# slave.net
KiCad netlist of a schematic drawn in Altium Designer
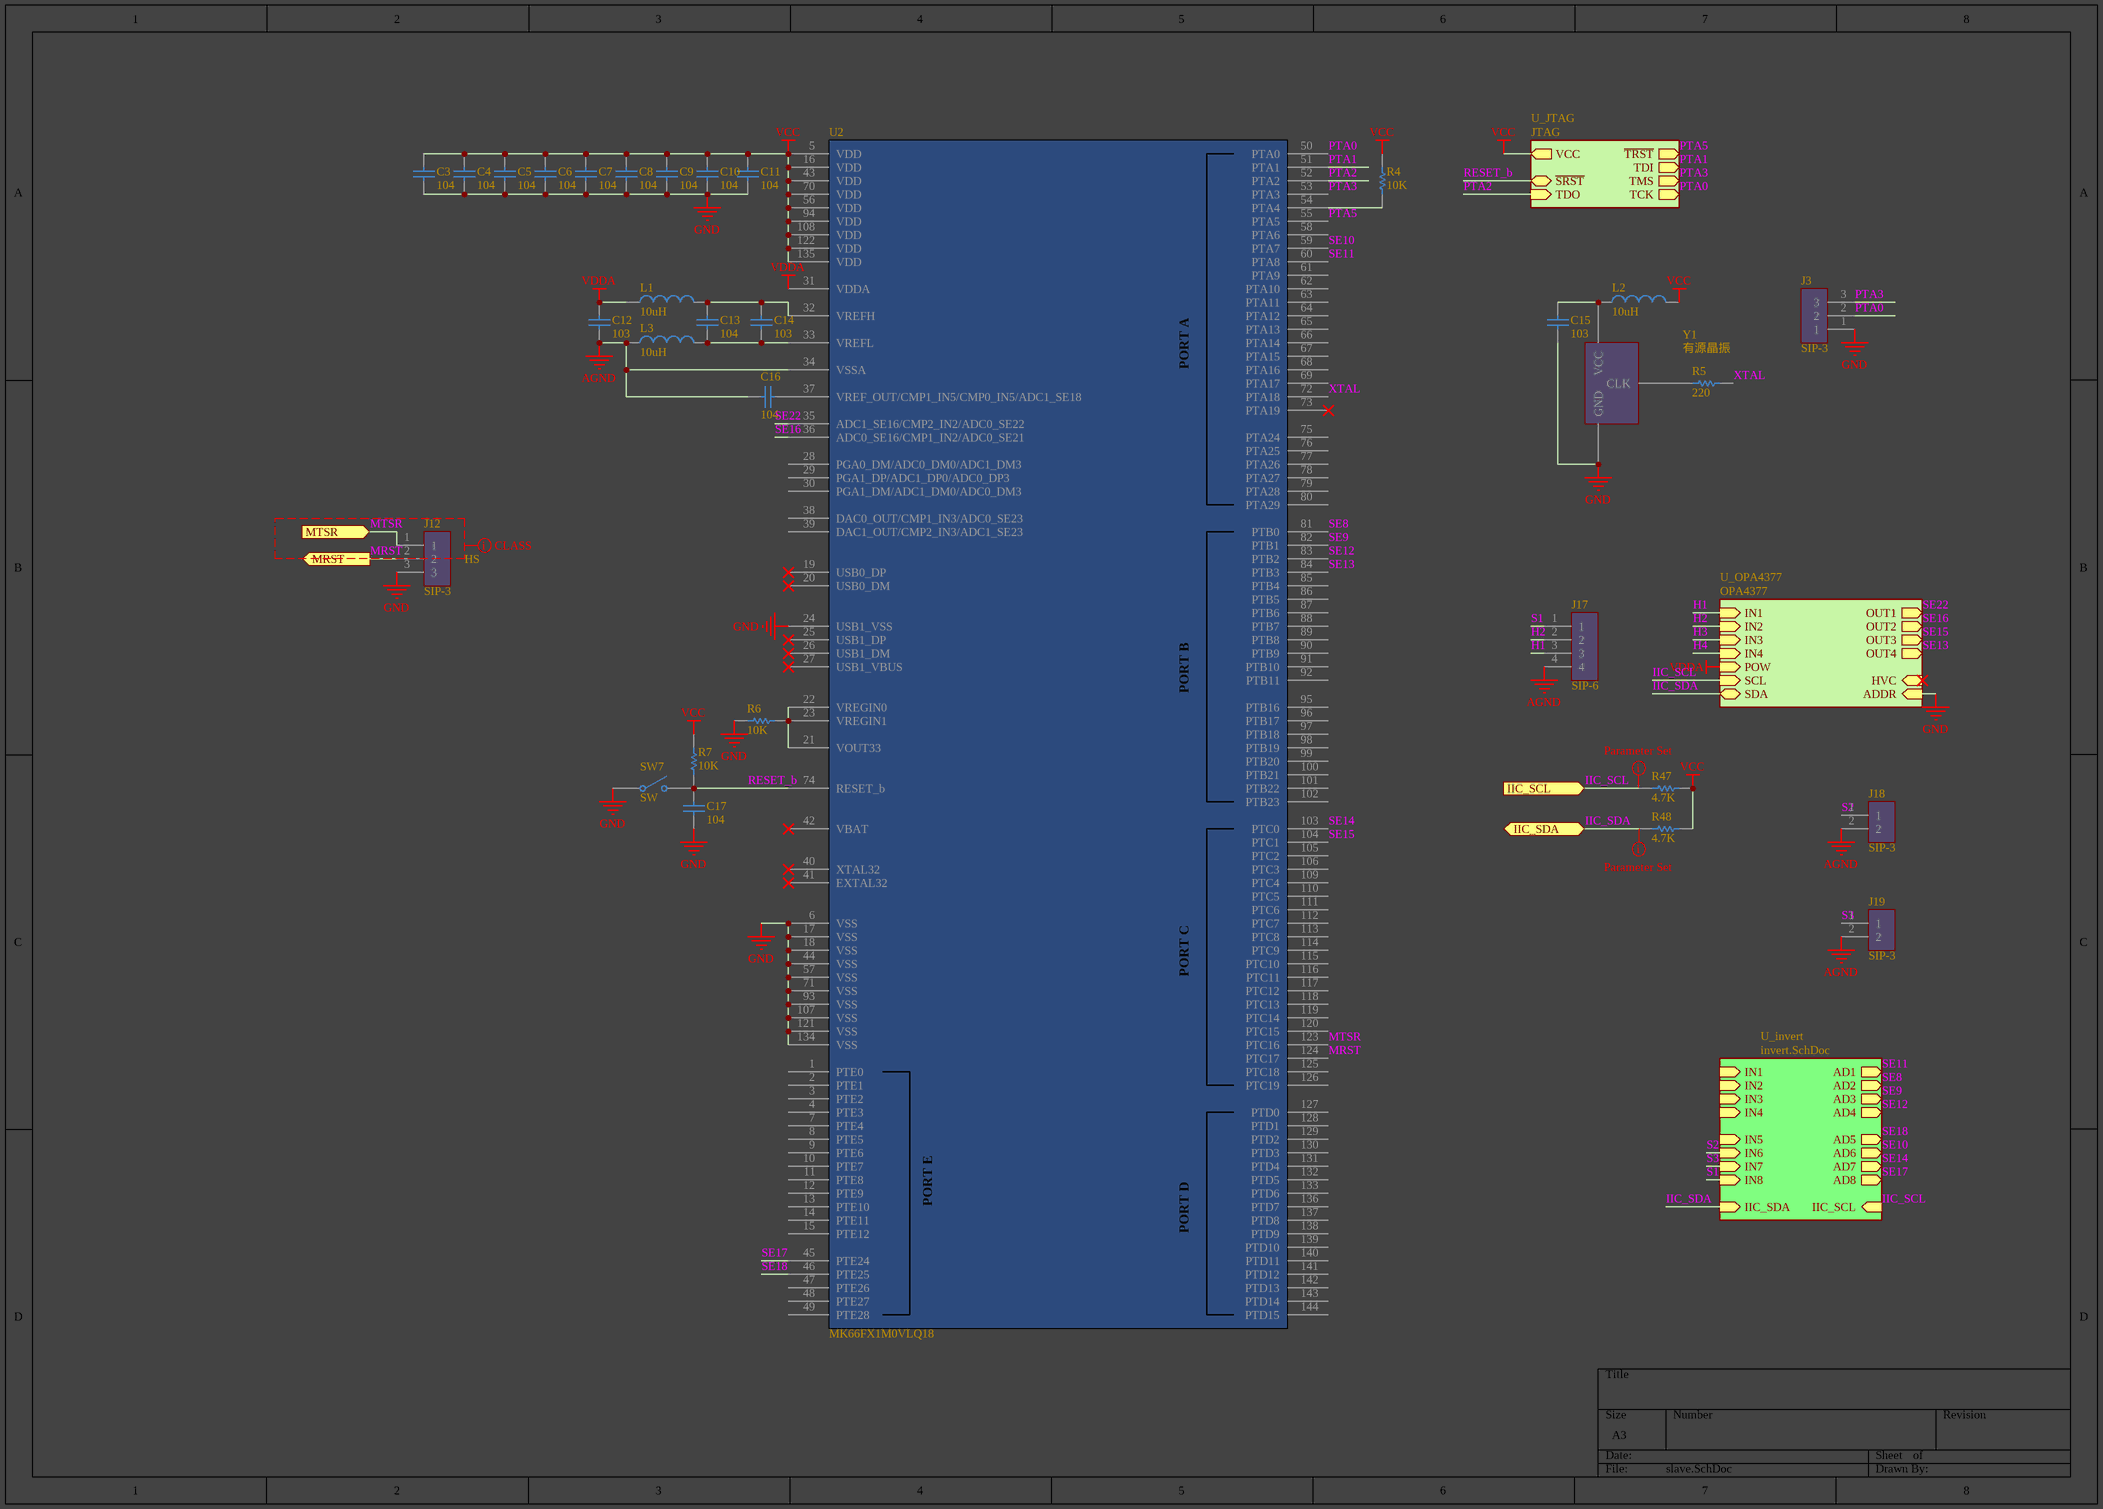
[diagram p0: slave.SchDoc]

(export (version "E")
  (design (tool "Eeschema 10.0.6"))
  (components
    (comp (ref "C3")
      (value "104")
      (footprint "C0603")
      (description "Capacitor")
      (fields (field (name "PUBLISHER") "Altium Limited"))
      (libsource (lib "iMag") (part "电容"))
    )
    (comp (ref "C4")
      (value "104")
      (footprint "C0603")
      (description "Capacitor")
      (fields (field (name "PUBLISHER") "Altium Limited"))
      (libsource (lib "iMag") (part "电容"))
    )
    (comp (ref "C5")
      (value "104")
      (footprint "C0603")
      (description "Capacitor")
      (fields (field (name "PUBLISHER") "Altium Limited"))
      (libsource (lib "iMag") (part "电容"))
    )
    (comp (ref "C6")
      (value "104")
      (footprint "C0603")
      (description "Capacitor")
      (fields (field (name "PUBLISHER") "Altium Limited"))
      (libsource (lib "iMag") (part "电容"))
    )
    (comp (ref "C7")
      (value "104")
      (footprint "C0603")
      (description "Capacitor")
      (fields (field (name "PUBLISHER") "Altium Limited"))
      (libsource (lib "iMag") (part "电容"))
    )
    (comp (ref "C8")
      (value "104")
      (footprint "C0603")
      (description "Capacitor")
      (fields (field (name "PUBLISHER") "Altium Limited"))
      (libsource (lib "iMag") (part "电容"))
    )
    (comp (ref "C9")
      (value "104")
      (footprint "C0603")
      (description "Capacitor")
      (fields (field (name "PUBLISHER") "Altium Limited"))
      (libsource (lib "iMag") (part "电容"))
    )
    (comp (ref "C10")
      (value "104")
      (footprint "C0603")
      (description "Capacitor")
      (fields (field (name "PUBLISHER") "Altium Limited"))
      (libsource (lib "iMag") (part "电容"))
    )
    (comp (ref "C11")
      (value "104")
      (footprint "C0603")
      (description "Capacitor")
      (fields (field (name "PUBLISHER") "Altium Limited"))
      (libsource (lib "iMag") (part "电容"))
    )
    (comp (ref "C12")
      (value "103")
      (footprint "C0603")
      (description "Capacitor")
      (fields (field (name "PUBLISHER") "Altium Limited"))
      (libsource (lib "iMag") (part "电容"))
    )
    (comp (ref "C13")
      (value "104")
      (footprint "C0603")
      (description "Capacitor")
      (fields (field (name "PUBLISHER") "Altium Limited"))
      (libsource (lib "iMag") (part "电容"))
    )
    (comp (ref "C14")
      (value "103")
      (footprint "C0603")
      (description "Capacitor")
      (fields (field (name "PUBLISHER") "Altium Limited"))
      (libsource (lib "iMag") (part "电容"))
    )
    (comp (ref "C15")
      (value "103")
      (footprint "C0603")
      (description "Capacitor")
      (fields (field (name "PUBLISHER") "Altium Limited"))
      (libsource (lib "iMag") (part "电容"))
    )
    (comp (ref "C16")
      (value "104")
      (footprint "C0402")
      (description "Capacitor")
      (fields (field (name "PUBLISHER") "Altium Limited"))
      (libsource (lib "iMag") (part "电容"))
    )
    (comp (ref "C17")
      (value "104")
      (footprint "C0603")
      (description "Capacitor")
      (fields (field (name "PUBLISHER") "Altium Limited"))
      (libsource (lib "iMag") (part "电容"))
    )
    (comp (ref "J3") (value "SIP-3") (footprint "2.0排针3P") (libsource (lib "iMag") (part "SIP-3")))
    (comp (ref "J12") (value "SIP-3") (footprint "2.0排针3P") (libsource (lib "") (part "SIP-3_1")))
    (comp (ref "J17") (value "SIP-6") (footprint "2.0排针4P") (libsource (lib "iMag") (part "SIP-4")))
    (comp (ref "J18") (value "SIP-3") (footprint "GH1.25-2P") (libsource (lib "iMag") (part "SIP-2")))
    (comp (ref "J19") (value "SIP-3") (footprint "GH1.25-2P") (libsource (lib "iMag") (part "SIP-2")))
    (comp (ref "L1") (value "10uH") (footprint "L0603") (libsource (lib "iMag") (part "电感")))
    (comp (ref "L2") (value "10uH") (footprint "L0603") (libsource (lib "iMag") (part "电感")))
    (comp (ref "L3") (value "10uH") (footprint "L0603") (libsource (lib "iMag") (part "电感")))
    (comp (ref "R4")
      (value "10K")
      (footprint "R0603")
      (description "Resistor")
      (fields (field (name "PUBLISHER") "Altium Limited"))
      (libsource (lib "iMag") (part "电阻"))
    )
    (comp (ref "R5")
      (value "220")
      (footprint "R0402")
      (description "Resistor")
      (fields (field (name "PUBLISHER") "Altium Limited"))
      (libsource (lib "iMag") (part "电阻"))
    )
    (comp (ref "R6")
      (value "10K")
      (footprint "R0603")
      (description "Resistor")
      (fields (field (name "PUBLISHER") "Altium Limited"))
      (libsource (lib "iMag") (part "电阻"))
    )
    (comp (ref "R7")
      (value "10K")
      (footprint "R0603")
      (description "Resistor")
      (fields (field (name "PUBLISHER") "Altium Limited"))
      (libsource (lib "iMag") (part "电阻"))
    )
    (comp (ref "R47")
      (value "4.7K")
      (footprint "R0603")
      (description "Resistor")
      (fields (field (name "PUBLISHER") "Altium Limited"))
      (libsource (lib "iMag") (part "电阻"))
    )
    (comp (ref "R48")
      (value "4.7K")
      (footprint "R0603")
      (description "Resistor")
      (fields (field (name "PUBLISHER") "Altium Limited"))
      (libsource (lib "iMag") (part "电阻"))
    )
    (comp (ref "SW7")
      (value "SW")
      (footprint "按键微动开关2")
      (description "Single-Pole, Single-Throw Switch")
      (libsource (lib "iMag") (part "Switch"))
    )
    (comp (ref "U2")
      (value "MK66FX1M0VLQ18")
      (footprint "LQFP144 20X20")
      (libsource (lib "iMag") (part "MK66"))
    )
    (comp (ref "Y1") (value "有源晶振") (footprint "OSC 5032-4P") (libsource (lib "iMag") (part "有源晶振")))
  )
  (nets
    (net (code "1") (name "/H1") (class "Default")
      (node (ref "J17") (pin "3") (pinfunction "3_3") (pintype "passive"))
    )
    (net (code "2") (name "/H2") (class "Default")
      (node (ref "J17") (pin "2") (pinfunction "2_2") (pintype "passive"))
    )
    (net (code "6") (name "/IIC_SCL") (class "Default")
      (node (ref "R47") (pin "2") (pinfunction "2_2") (pintype "passive"))
    )
    (net (code "7") (name "/IIC_SDA") (class "Default")
      (node (ref "R48") (pin "2") (pinfunction "2_2") (pintype "passive"))
    )
    (net (code "13") (name "/MRST") (class "Default")
      (node (ref "J12") (pin "2") (pinfunction "2_2") (pintype "passive"))
      (node (ref "U2") (pin "124") (pinfunction "PTC17_124") (pintype "passive"))
    )
    (net (code "14") (name "/MTSR") (class "Default")
      (node (ref "J12") (pin "1") (pinfunction "1_1") (pintype "passive"))
      (node (ref "U2") (pin "123") (pinfunction "PTC16_123") (pintype "passive"))
    )
    (net (code "15") (name "/PTA0") (class "Default")
      (node (ref "J3") (pin "2") (pinfunction "2_2") (pintype "passive"))
      (node (ref "U2") (pin "50") (pinfunction "PTA0_50") (pintype "passive"))
    )
    (net (code "16") (name "/PTA1") (class "Default")
      (node (ref "U2") (pin "51") (pinfunction "PTA1_51") (pintype "passive"))
    )
    (net (code "17") (name "/PTA2") (class "Default")
      (node (ref "U2") (pin "52") (pinfunction "PTA2_52") (pintype "passive"))
    )
    (net (code "18") (name "/PTA3") (class "Default")
      (node (ref "J3") (pin "3") (pinfunction "3_3") (pintype "passive"))
      (node (ref "U2") (pin "53") (pinfunction "PTA3_53") (pintype "passive"))
    )
    (net (code "19") (name "/PTA5") (class "Default")
      (node (ref "U2") (pin "55") (pinfunction "PTA5_55") (pintype "passive"))
    )
    (net (code "20") (name "/RESET_b") (class "Default")
      (node (ref "C17") (pin "2") (pinfunction "2_2") (pintype "passive"))
      (node (ref "R7") (pin "1") (pinfunction "1_1") (pintype "passive"))
      (node (ref "SW7") (pin "2") (pinfunction "NO_2") (pintype "passive"))
      (node (ref "U2") (pin "74") (pinfunction "RESET_b_74") (pintype "passive"))
    )
    (net (code "21") (name "/S1") (class "Default")
      (node (ref "J17") (pin "1") (pinfunction "1_1") (pintype "passive"))
    )
    (net (code "22") (name "/S2") (class "Default")
      (node (ref "J18") (pin "1") (pinfunction "1_1") (pintype "passive"))
    )
    (net (code "23") (name "/S3") (class "Default")
      (node (ref "J19") (pin "1") (pinfunction "1_1") (pintype "passive"))
    )
    (net (code "24") (name "/SE8") (class "Default")
      (node (ref "U2") (pin "81") (pinfunction "PTB0_81") (pintype "passive"))
    )
    (net (code "25") (name "/SE9") (class "Default")
      (node (ref "U2") (pin "82") (pinfunction "PTB1_82") (pintype "passive"))
    )
    (net (code "26") (name "/SE10") (class "Default")
      (node (ref "U2") (pin "59") (pinfunction "PTA7_59") (pintype "passive"))
    )
    (net (code "27") (name "/SE11") (class "Default")
      (node (ref "U2") (pin "60") (pinfunction "PTA8_60") (pintype "passive"))
    )
    (net (code "28") (name "/SE12") (class "Default")
      (node (ref "U2") (pin "83") (pinfunction "PTB2_83") (pintype "passive"))
    )
    (net (code "29") (name "/SE13") (class "Default")
      (node (ref "U2") (pin "84") (pinfunction "PTB3_84") (pintype "passive"))
    )
    (net (code "30") (name "/SE14") (class "Default")
      (node (ref "U2") (pin "103") (pinfunction "PTC0_103") (pintype "passive"))
    )
    (net (code "31") (name "/SE15") (class "Default")
      (node (ref "U2") (pin "104") (pinfunction "PTC1_104") (pintype "passive"))
    )
    (net (code "32") (name "/SE16") (class "Default")
      (node (ref "U2") (pin "36") (pinfunction "ADC0_SE16/CMP1_IN2/ADC0_SE21_36") (pintype "passive"))
    )
    (net (code "33") (name "/SE17") (class "Default")
      (node (ref "U2") (pin "45") (pinfunction "PTE24_45") (pintype "passive"))
    )
    (net (code "34") (name "/SE18") (class "Default")
      (node (ref "U2") (pin "46") (pinfunction "PTE25_46") (pintype "passive"))
    )
    (net (code "35") (name "/SE22") (class "Default")
      (node (ref "U2") (pin "35") (pinfunction "ADC1_SE16/CMP2_IN2/ADC0_SE22_35") (pintype "passive"))
    )
    (net (code "36") (name "/XTAL") (class "Default")
      (node (ref "R5") (pin "1") (pinfunction "1_1") (pintype "passive"))
      (node (ref "U2") (pin "72") (pinfunction "PTA18_72") (pintype "passive"))
    )
    (net (code "37") (name "AGND") (class "Default")
      (node (ref "C12") (pin "1") (pinfunction "1_1") (pintype "passive"))
      (node (ref "C16") (pin "1") (pinfunction "1_1") (pintype "passive"))
      (node (ref "J17") (pin "4") (pinfunction "4_4") (pintype "passive"))
      (node (ref "J18") (pin "2") (pinfunction "2_2") (pintype "passive"))
      (node (ref "J19") (pin "2") (pinfunction "2_2") (pintype "passive"))
      (node (ref "L3") (pin "1") (pinfunction "1_1") (pintype "passive"))
      (node (ref "U2") (pin "34") (pinfunction "VSSA_34") (pintype "passive"))
    )
    (net (code "38") (name "GND") (class "Default")
      (node (ref "C10") (pin "1") (pinfunction "1_1") (pintype "passive"))
      (node (ref "C11") (pin "1") (pinfunction "1_1") (pintype "passive"))
      (node (ref "C15") (pin "1") (pinfunction "1_1") (pintype "passive"))
      (node (ref "C17") (pin "1") (pinfunction "1_1") (pintype "passive"))
      (node (ref "C3") (pin "1") (pinfunction "1_1") (pintype "passive"))
      (node (ref "C4") (pin "1") (pinfunction "1_1") (pintype "passive"))
      (node (ref "C5") (pin "1") (pinfunction "1_1") (pintype "passive"))
      (node (ref "C6") (pin "1") (pinfunction "1_1") (pintype "passive"))
      (node (ref "C7") (pin "1") (pinfunction "1_1") (pintype "passive"))
      (node (ref "C8") (pin "1") (pinfunction "1_1") (pintype "passive"))
      (node (ref "C9") (pin "1") (pinfunction "1_1") (pintype "passive"))
      (node (ref "J12") (pin "3") (pinfunction "3_3") (pintype "passive"))
      (node (ref "J3") (pin "1") (pinfunction "1_1") (pintype "passive"))
      (node (ref "R6") (pin "2") (pinfunction "2_2") (pintype "passive"))
      (node (ref "SW7") (pin "1") (pinfunction "COMMON_1") (pintype "passive"))
      (node (ref "U2") (pin "107") (pinfunction "VSS_107") (pintype "passive"))
      (node (ref "U2") (pin "121") (pinfunction "VSS_121") (pintype "passive"))
      (node (ref "U2") (pin "134") (pinfunction "VSS_134") (pintype "passive"))
      (node (ref "U2") (pin "17") (pinfunction "VSS_17") (pintype "passive"))
      (node (ref "U2") (pin "18") (pinfunction "VSS_18") (pintype "passive"))
      (node (ref "U2") (pin "24") (pinfunction "USB1_VSS_24") (pintype "passive"))
      (node (ref "U2") (pin "44") (pinfunction "VSS_44") (pintype "passive"))
      (node (ref "U2") (pin "57") (pinfunction "VSS_57") (pintype "passive"))
      (node (ref "U2") (pin "6") (pinfunction "VSS_6") (pintype "passive"))
      (node (ref "U2") (pin "71") (pinfunction "VSS_71") (pintype "passive"))
      (node (ref "U2") (pin "93") (pinfunction "VSS_93") (pintype "passive"))
      (node (ref "Y1") (pin "2") (pinfunction "GND_2") (pintype "passive"))
    )
    (net (code "39") (name "Net-(U2-PTA4)") (class "Default")
      (node (ref "R4") (pin "2") (pinfunction "2_2") (pintype "passive"))
      (node (ref "U2") (pin "54") (pinfunction "PTA4_54") (pintype "passive"))
    )
    (net (code "40") (name "Net-(U2-VOUT33)") (class "Default")
      (node (ref "R6") (pin "1") (pinfunction "1_1") (pintype "passive"))
      (node (ref "U2") (pin "21") (pinfunction "VOUT33_21") (pintype "passive"))
      (node (ref "U2") (pin "22") (pinfunction "VREGIN0_22") (pintype "passive"))
      (node (ref "U2") (pin "23") (pinfunction "VREGIN1_23") (pintype "passive"))
    )
    (net (code "41") (name "Net-(U2-VREFH)") (class "Default")
      (node (ref "C13") (pin "2") (pinfunction "2_2") (pintype "passive"))
      (node (ref "C14") (pin "2") (pinfunction "2_2") (pintype "passive"))
      (node (ref "L1") (pin "2") (pinfunction "2_2") (pintype "passive"))
      (node (ref "U2") (pin "32") (pinfunction "VREFH_32") (pintype "passive"))
    )
    (net (code "42") (name "Net-(U2-VREFL)") (class "Default")
      (node (ref "C13") (pin "1") (pinfunction "1_1") (pintype "passive"))
      (node (ref "C14") (pin "1") (pinfunction "1_1") (pintype "passive"))
      (node (ref "L3") (pin "2") (pinfunction "2_2") (pintype "passive"))
      (node (ref "U2") (pin "33") (pinfunction "VREFL_33") (pintype "passive"))
    )
    (net (code "43") (name "Net-(U2-VREF_OUT{slash}CMP1_IN5{slash}CMP0_IN5{slash}ADC1_SE18)") (class "Default")
      (node (ref "C16") (pin "2") (pinfunction "2_2") (pintype "passive"))
      (node (ref "U2") (pin "37") (pinfunction "VREF_OUT/CMP1_IN5/CMP0_IN5/ADC1_SE18_37") (pintype "passive"))
    )
    (net (code "44") (name "Net-(Y1-CLK)") (class "Default")
      (node (ref "R5") (pin "2") (pinfunction "2_2") (pintype "passive"))
      (node (ref "Y1") (pin "3") (pinfunction "CLK_3") (pintype "passive"))
    )
    (net (code "45") (name "Net-(Y1-VCC)") (class "Default")
      (node (ref "C15") (pin "2") (pinfunction "2_2") (pintype "passive"))
      (node (ref "L2") (pin "1") (pinfunction "1_1") (pintype "passive"))
      (node (ref "Y1") (pin "4") (pinfunction "VCC_4") (pintype "passive"))
    )
    (net (code "46") (name "VCC") (class "Default")
      (node (ref "C10") (pin "2") (pinfunction "2_2") (pintype "passive"))
      (node (ref "C11") (pin "2") (pinfunction "2_2") (pintype "passive"))
      (node (ref "C3") (pin "2") (pinfunction "2_2") (pintype "passive"))
      (node (ref "C4") (pin "2") (pinfunction "2_2") (pintype "passive"))
      (node (ref "C5") (pin "2") (pinfunction "2_2") (pintype "passive"))
      (node (ref "C6") (pin "2") (pinfunction "2_2") (pintype "passive"))
      (node (ref "C7") (pin "2") (pinfunction "2_2") (pintype "passive"))
      (node (ref "C8") (pin "2") (pinfunction "2_2") (pintype "passive"))
      (node (ref "C9") (pin "2") (pinfunction "2_2") (pintype "passive"))
      (node (ref "L2") (pin "2") (pinfunction "2_2") (pintype "passive"))
      (node (ref "R4") (pin "1") (pinfunction "1_1") (pintype "passive"))
      (node (ref "R47") (pin "1") (pinfunction "1_1") (pintype "passive"))
      (node (ref "R48") (pin "1") (pinfunction "1_1") (pintype "passive"))
      (node (ref "R7") (pin "2") (pinfunction "2_2") (pintype "passive"))
      (node (ref "U2") (pin "108") (pinfunction "VDD_108") (pintype "passive"))
      (node (ref "U2") (pin "122") (pinfunction "VDD_122") (pintype "passive"))
      (node (ref "U2") (pin "135") (pinfunction "VDD_135") (pintype "passive"))
      (node (ref "U2") (pin "16") (pinfunction "VDD_16") (pintype "passive"))
      (node (ref "U2") (pin "43") (pinfunction "VDD_43") (pintype "passive"))
      (node (ref "U2") (pin "5") (pinfunction "VDD_5") (pintype "passive"))
      (node (ref "U2") (pin "56") (pinfunction "VDD_56") (pintype "passive"))
      (node (ref "U2") (pin "70") (pinfunction "VDD_70") (pintype "passive"))
      (node (ref "U2") (pin "94") (pinfunction "VDD_94") (pintype "passive"))
    )
    (net (code "47") (name "VDDA") (class "Default")
      (node (ref "C12") (pin "2") (pinfunction "2_2") (pintype "passive"))
      (node (ref "L1") (pin "1") (pinfunction "1_1") (pintype "passive"))
      (node (ref "U2") (pin "31") (pinfunction "VDDA_31") (pintype "passive"))
    )
    (net (code "48") (name "unconnected-(U2-DAC0_OUT{slash}CMP1_IN3{slash}ADC0_SE23-Pad38)") (class "Default")
      (node (ref "U2") (pin "38") (pinfunction "DAC0_OUT/CMP1_IN3/ADC0_SE23_38") (pintype "passive"))
    )
    (net (code "49") (name "unconnected-(U2-DAC1_OUT{slash}CMP2_IN3{slash}ADC1_SE23-Pad39)") (class "Default")
      (node (ref "U2") (pin "39") (pinfunction "DAC1_OUT/CMP2_IN3/ADC1_SE23_39") (pintype "passive"))
    )
    (net (code "50") (name "unconnected-(U2-EXTAL32-Pad41)") (class "Default")
      (node (ref "U2") (pin "41") (pinfunction "EXTAL32_41") (pintype "passive+no_connect"))
    )
    (net (code "51") (name "unconnected-(U2-PGA0_DM{slash}ADC0_DM0{slash}ADC1_DM3-Pad28)") (class "Default")
      (node (ref "U2") (pin "28") (pinfunction "PGA0_DM/ADC0_DM0/ADC1_DM3_28") (pintype "passive"))
    )
    (net (code "52") (name "unconnected-(U2-PGA1_DM{slash}ADC1_DM0{slash}ADC0_DM3-Pad30)") (class "Default")
      (node (ref "U2") (pin "30") (pinfunction "PGA1_DM/ADC1_DM0/ADC0_DM3_30") (pintype "passive"))
    )
    (net (code "53") (name "unconnected-(U2-PGA1_DP{slash}ADC1_DP0{slash}ADC0_DP3-Pad29)") (class "Default")
      (node (ref "U2") (pin "29") (pinfunction "PGA1_DP/ADC1_DP0/ADC0_DP3_29") (pintype "passive"))
    )
    (net (code "54") (name "unconnected-(U2-PTA6-Pad58)") (class "Default")
      (node (ref "U2") (pin "58") (pinfunction "PTA6_58") (pintype "passive"))
    )
    (net (code "55") (name "unconnected-(U2-PTA9-Pad61)") (class "Default")
      (node (ref "U2") (pin "61") (pinfunction "PTA9_61") (pintype "passive"))
    )
    (net (code "56") (name "unconnected-(U2-PTA10-Pad62)") (class "Default")
      (node (ref "U2") (pin "62") (pinfunction "PTA10_62") (pintype "passive"))
    )
    (net (code "57") (name "unconnected-(U2-PTA11-Pad63)") (class "Default")
      (node (ref "U2") (pin "63") (pinfunction "PTA11_63") (pintype "passive"))
    )
    (net (code "58") (name "unconnected-(U2-PTA12-Pad64)") (class "Default")
      (node (ref "U2") (pin "64") (pinfunction "PTA12_64") (pintype "passive"))
    )
    (net (code "59") (name "unconnected-(U2-PTA13-Pad65)") (class "Default")
      (node (ref "U2") (pin "65") (pinfunction "PTA13_65") (pintype "passive"))
    )
    (net (code "60") (name "unconnected-(U2-PTA14-Pad66)") (class "Default")
      (node (ref "U2") (pin "66") (pinfunction "PTA14_66") (pintype "passive"))
    )
    (net (code "61") (name "unconnected-(U2-PTA15-Pad67)") (class "Default")
      (node (ref "U2") (pin "67") (pinfunction "PTA15_67") (pintype "passive"))
    )
    (net (code "62") (name "unconnected-(U2-PTA16-Pad68)") (class "Default")
      (node (ref "U2") (pin "68") (pinfunction "PTA16_68") (pintype "passive"))
    )
    (net (code "63") (name "unconnected-(U2-PTA17-Pad69)") (class "Default")
      (node (ref "U2") (pin "69") (pinfunction "PTA17_69") (pintype "passive"))
    )
    (net (code "64") (name "unconnected-(U2-PTA19-Pad73)") (class "Default")
      (node (ref "U2") (pin "73") (pinfunction "PTA19_73") (pintype "passive+no_connect"))
    )
    (net (code "65") (name "unconnected-(U2-PTA24-Pad75)") (class "Default")
      (node (ref "U2") (pin "75") (pinfunction "PTA24_75") (pintype "passive"))
    )
    (net (code "66") (name "unconnected-(U2-PTA25-Pad76)") (class "Default")
      (node (ref "U2") (pin "76") (pinfunction "PTA25_76") (pintype "passive"))
    )
    (net (code "67") (name "unconnected-(U2-PTA26-Pad77)") (class "Default")
      (node (ref "U2") (pin "77") (pinfunction "PTA26_77") (pintype "passive"))
    )
    (net (code "68") (name "unconnected-(U2-PTA27-Pad78)") (class "Default")
      (node (ref "U2") (pin "78") (pinfunction "PTA27_78") (pintype "passive"))
    )
    (net (code "69") (name "unconnected-(U2-PTA28-Pad79)") (class "Default")
      (node (ref "U2") (pin "79") (pinfunction "PTA28_79") (pintype "passive"))
    )
    (net (code "70") (name "unconnected-(U2-PTA29-Pad80)") (class "Default")
      (node (ref "U2") (pin "80") (pinfunction "PTA29_80") (pintype "passive"))
    )
    (net (code "71") (name "unconnected-(U2-PTB4-Pad85)") (class "Default")
      (node (ref "U2") (pin "85") (pinfunction "PTB4_85") (pintype "passive"))
    )
    (net (code "72") (name "unconnected-(U2-PTB5-Pad86)") (class "Default")
      (node (ref "U2") (pin "86") (pinfunction "PTB5_86") (pintype "passive"))
    )
    (net (code "73") (name "unconnected-(U2-PTB6-Pad87)") (class "Default")
      (node (ref "U2") (pin "87") (pinfunction "PTB6_87") (pintype "passive"))
    )
    (net (code "74") (name "unconnected-(U2-PTB7-Pad88)") (class "Default")
      (node (ref "U2") (pin "88") (pinfunction "PTB7_88") (pintype "passive"))
    )
    (net (code "75") (name "unconnected-(U2-PTB8-Pad89)") (class "Default")
      (node (ref "U2") (pin "89") (pinfunction "PTB8_89") (pintype "passive"))
    )
    (net (code "76") (name "unconnected-(U2-PTB9-Pad90)") (class "Default")
      (node (ref "U2") (pin "90") (pinfunction "PTB9_90") (pintype "passive"))
    )
    (net (code "77") (name "unconnected-(U2-PTB10-Pad91)") (class "Default")
      (node (ref "U2") (pin "91") (pinfunction "PTB10_91") (pintype "passive"))
    )
    (net (code "78") (name "unconnected-(U2-PTB11-Pad92)") (class "Default")
      (node (ref "U2") (pin "92") (pinfunction "PTB11_92") (pintype "passive"))
    )
    (net (code "79") (name "unconnected-(U2-PTB16-Pad95)") (class "Default")
      (node (ref "U2") (pin "95") (pinfunction "PTB16_95") (pintype "passive"))
    )
    (net (code "80") (name "unconnected-(U2-PTB17-Pad96)") (class "Default")
      (node (ref "U2") (pin "96") (pinfunction "PTB17_96") (pintype "passive"))
    )
    (net (code "81") (name "unconnected-(U2-PTB18-Pad97)") (class "Default")
      (node (ref "U2") (pin "97") (pinfunction "PTB18_97") (pintype "passive"))
    )
    (net (code "82") (name "unconnected-(U2-PTB19-Pad98)") (class "Default")
      (node (ref "U2") (pin "98") (pinfunction "PTB19_98") (pintype "passive"))
    )
    (net (code "83") (name "unconnected-(U2-PTB20-Pad99)") (class "Default")
      (node (ref "U2") (pin "99") (pinfunction "PTB20_99") (pintype "passive"))
    )
    (net (code "84") (name "unconnected-(U2-PTB21-Pad100)") (class "Default")
      (node (ref "U2") (pin "100") (pinfunction "PTB21_100") (pintype "passive"))
    )
    (net (code "85") (name "unconnected-(U2-PTB22-Pad101)") (class "Default")
      (node (ref "U2") (pin "101") (pinfunction "PTB22_101") (pintype "passive"))
    )
    (net (code "86") (name "unconnected-(U2-PTB23-Pad102)") (class "Default")
      (node (ref "U2") (pin "102") (pinfunction "PTB23_102") (pintype "passive"))
    )
    (net (code "87") (name "unconnected-(U2-PTC2-Pad105)") (class "Default")
      (node (ref "U2") (pin "105") (pinfunction "PTC2_105") (pintype "passive"))
    )
    (net (code "88") (name "unconnected-(U2-PTC3-Pad106)") (class "Default")
      (node (ref "U2") (pin "106") (pinfunction "PTC3_106") (pintype "passive"))
    )
    (net (code "89") (name "unconnected-(U2-PTC4-Pad109)") (class "Default")
      (node (ref "U2") (pin "109") (pinfunction "PTC4_109") (pintype "passive"))
    )
    (net (code "90") (name "unconnected-(U2-PTC5-Pad110)") (class "Default")
      (node (ref "U2") (pin "110") (pinfunction "PTC5_110") (pintype "passive"))
    )
    (net (code "91") (name "unconnected-(U2-PTC6-Pad111)") (class "Default")
      (node (ref "U2") (pin "111") (pinfunction "PTC6_111") (pintype "passive"))
    )
    (net (code "92") (name "unconnected-(U2-PTC7-Pad112)") (class "Default")
      (node (ref "U2") (pin "112") (pinfunction "PTC7_112") (pintype "passive"))
    )
    (net (code "93") (name "unconnected-(U2-PTC8-Pad113)") (class "Default")
      (node (ref "U2") (pin "113") (pinfunction "PTC8_113") (pintype "passive"))
    )
    (net (code "94") (name "unconnected-(U2-PTC9-Pad114)") (class "Default")
      (node (ref "U2") (pin "114") (pinfunction "PTC9_114") (pintype "passive"))
    )
    (net (code "95") (name "unconnected-(U2-PTC10-Pad115)") (class "Default")
      (node (ref "U2") (pin "115") (pinfunction "PTC10_115") (pintype "passive"))
    )
    (net (code "96") (name "unconnected-(U2-PTC11-Pad116)") (class "Default")
      (node (ref "U2") (pin "116") (pinfunction "PTC11_116") (pintype "passive"))
    )
    (net (code "97") (name "unconnected-(U2-PTC12-Pad117)") (class "Default")
      (node (ref "U2") (pin "117") (pinfunction "PTC12_117") (pintype "passive"))
    )
    (net (code "98") (name "unconnected-(U2-PTC13-Pad118)") (class "Default")
      (node (ref "U2") (pin "118") (pinfunction "PTC13_118") (pintype "passive"))
    )
    (net (code "99") (name "unconnected-(U2-PTC14-Pad119)") (class "Default")
      (node (ref "U2") (pin "119") (pinfunction "PTC14_119") (pintype "passive"))
    )
    (net (code "100") (name "unconnected-(U2-PTC15-Pad120)") (class "Default")
      (node (ref "U2") (pin "120") (pinfunction "PTC15_120") (pintype "passive"))
    )
    (net (code "101") (name "unconnected-(U2-PTC18-Pad125)") (class "Default")
      (node (ref "U2") (pin "125") (pinfunction "PTC18_125") (pintype "passive"))
    )
    (net (code "102") (name "unconnected-(U2-PTC19-Pad126)") (class "Default")
      (node (ref "U2") (pin "126") (pinfunction "PTC19_126") (pintype "passive"))
    )
    (net (code "103") (name "unconnected-(U2-PTD0-Pad127)") (class "Default")
      (node (ref "U2") (pin "127") (pinfunction "PTD0_127") (pintype "passive"))
    )
    (net (code "104") (name "unconnected-(U2-PTD1-Pad128)") (class "Default")
      (node (ref "U2") (pin "128") (pinfunction "PTD1_128") (pintype "passive"))
    )
    (net (code "105") (name "unconnected-(U2-PTD2-Pad129)") (class "Default")
      (node (ref "U2") (pin "129") (pinfunction "PTD2_129") (pintype "passive"))
    )
    (net (code "106") (name "unconnected-(U2-PTD3-Pad130)") (class "Default")
      (node (ref "U2") (pin "130") (pinfunction "PTD3_130") (pintype "passive"))
    )
    (net (code "107") (name "unconnected-(U2-PTD4-Pad131)") (class "Default")
      (node (ref "U2") (pin "131") (pinfunction "PTD4_131") (pintype "passive"))
    )
    (net (code "108") (name "unconnected-(U2-PTD5-Pad132)") (class "Default")
      (node (ref "U2") (pin "132") (pinfunction "PTD5_132") (pintype "passive"))
    )
    (net (code "109") (name "unconnected-(U2-PTD6-Pad133)") (class "Default")
      (node (ref "U2") (pin "133") (pinfunction "PTD6_133") (pintype "passive"))
    )
    (net (code "110") (name "unconnected-(U2-PTD7-Pad136)") (class "Default")
      (node (ref "U2") (pin "136") (pinfunction "PTD7_136") (pintype "passive"))
    )
    (net (code "111") (name "unconnected-(U2-PTD8-Pad137)") (class "Default")
      (node (ref "U2") (pin "137") (pinfunction "PTD8_137") (pintype "passive"))
    )
    (net (code "112") (name "unconnected-(U2-PTD9-Pad138)") (class "Default")
      (node (ref "U2") (pin "138") (pinfunction "PTD9_138") (pintype "passive"))
    )
    (net (code "113") (name "unconnected-(U2-PTD10-Pad139)") (class "Default")
      (node (ref "U2") (pin "139") (pinfunction "PTD10_139") (pintype "passive"))
    )
    (net (code "114") (name "unconnected-(U2-PTD11-Pad140)") (class "Default")
      (node (ref "U2") (pin "140") (pinfunction "PTD11_140") (pintype "passive"))
    )
    (net (code "115") (name "unconnected-(U2-PTD12-Pad141)") (class "Default")
      (node (ref "U2") (pin "141") (pinfunction "PTD12_141") (pintype "passive"))
    )
    (net (code "116") (name "unconnected-(U2-PTD13-Pad142)") (class "Default")
      (node (ref "U2") (pin "142") (pinfunction "PTD13_142") (pintype "passive"))
    )
    (net (code "117") (name "unconnected-(U2-PTD14-Pad143)") (class "Default")
      (node (ref "U2") (pin "143") (pinfunction "PTD14_143") (pintype "passive"))
    )
    (net (code "118") (name "unconnected-(U2-PTD15-Pad144)") (class "Default")
      (node (ref "U2") (pin "144") (pinfunction "PTD15_144") (pintype "passive"))
    )
    (net (code "119") (name "unconnected-(U2-PTE0-Pad1)") (class "Default")
      (node (ref "U2") (pin "1") (pinfunction "PTE0_1") (pintype "passive"))
    )
    (net (code "120") (name "unconnected-(U2-PTE1-Pad2)") (class "Default")
      (node (ref "U2") (pin "2") (pinfunction "PTE1_2") (pintype "passive"))
    )
    (net (code "121") (name "unconnected-(U2-PTE2-Pad3)") (class "Default")
      (node (ref "U2") (pin "3") (pinfunction "PTE2_3") (pintype "passive"))
    )
    (net (code "122") (name "unconnected-(U2-PTE3-Pad4)") (class "Default")
      (node (ref "U2") (pin "4") (pinfunction "PTE3_4") (pintype "passive"))
    )
    (net (code "123") (name "unconnected-(U2-PTE4-Pad7)") (class "Default")
      (node (ref "U2") (pin "7") (pinfunction "PTE4_7") (pintype "passive"))
    )
    (net (code "124") (name "unconnected-(U2-PTE5-Pad8)") (class "Default")
      (node (ref "U2") (pin "8") (pinfunction "PTE5_8") (pintype "passive"))
    )
    (net (code "125") (name "unconnected-(U2-PTE6-Pad9)") (class "Default")
      (node (ref "U2") (pin "9") (pinfunction "PTE6_9") (pintype "passive"))
    )
    (net (code "126") (name "unconnected-(U2-PTE7-Pad10)") (class "Default")
      (node (ref "U2") (pin "10") (pinfunction "PTE7_10") (pintype "passive"))
    )
    (net (code "127") (name "unconnected-(U2-PTE8-Pad11)") (class "Default")
      (node (ref "U2") (pin "11") (pinfunction "PTE8_11") (pintype "passive"))
    )
    (net (code "128") (name "unconnected-(U2-PTE9-Pad12)") (class "Default")
      (node (ref "U2") (pin "12") (pinfunction "PTE9_12") (pintype "passive"))
    )
    (net (code "129") (name "unconnected-(U2-PTE10-Pad13)") (class "Default")
      (node (ref "U2") (pin "13") (pinfunction "PTE10_13") (pintype "passive"))
    )
    (net (code "130") (name "unconnected-(U2-PTE11-Pad14)") (class "Default")
      (node (ref "U2") (pin "14") (pinfunction "PTE11_14") (pintype "passive"))
    )
    (net (code "131") (name "unconnected-(U2-PTE12-Pad15)") (class "Default")
      (node (ref "U2") (pin "15") (pinfunction "PTE12_15") (pintype "passive"))
    )
    (net (code "132") (name "unconnected-(U2-PTE26-Pad47)") (class "Default")
      (node (ref "U2") (pin "47") (pinfunction "PTE26_47") (pintype "passive"))
    )
    (net (code "133") (name "unconnected-(U2-PTE27-Pad48)") (class "Default")
      (node (ref "U2") (pin "48") (pinfunction "PTE27_48") (pintype "passive"))
    )
    (net (code "134") (name "unconnected-(U2-PTE28-Pad49)") (class "Default")
      (node (ref "U2") (pin "49") (pinfunction "PTE28_49") (pintype "passive"))
    )
    (net (code "135") (name "unconnected-(U2-USB0_DM-Pad20)") (class "Default")
      (node (ref "U2") (pin "20") (pinfunction "USB0_DM_20") (pintype "passive+no_connect"))
    )
    (net (code "136") (name "unconnected-(U2-USB0_DP-Pad19)") (class "Default")
      (node (ref "U2") (pin "19") (pinfunction "USB0_DP_19") (pintype "passive+no_connect"))
    )
    (net (code "137") (name "unconnected-(U2-USB1_DM-Pad26)") (class "Default")
      (node (ref "U2") (pin "26") (pinfunction "USB1_DM_26") (pintype "passive+no_connect"))
    )
    (net (code "138") (name "unconnected-(U2-USB1_DP-Pad25)") (class "Default")
      (node (ref "U2") (pin "25") (pinfunction "USB1_DP_25") (pintype "passive+no_connect"))
    )
    (net (code "139") (name "unconnected-(U2-USB1_VBUS-Pad27)") (class "Default")
      (node (ref "U2") (pin "27") (pinfunction "USB1_VBUS_27") (pintype "passive+no_connect"))
    )
    (net (code "140") (name "unconnected-(U2-VBAT-Pad42)") (class "Default")
      (node (ref "U2") (pin "42") (pinfunction "VBAT_42") (pintype "passive+no_connect"))
    )
    (net (code "141") (name "unconnected-(U2-XTAL32-Pad40)") (class "Default")
      (node (ref "U2") (pin "40") (pinfunction "XTAL32_40") (pintype "passive+no_connect"))
    )
  )
)
